# sensor.net
KiCad netlist of a schematic drawn in EAGLE
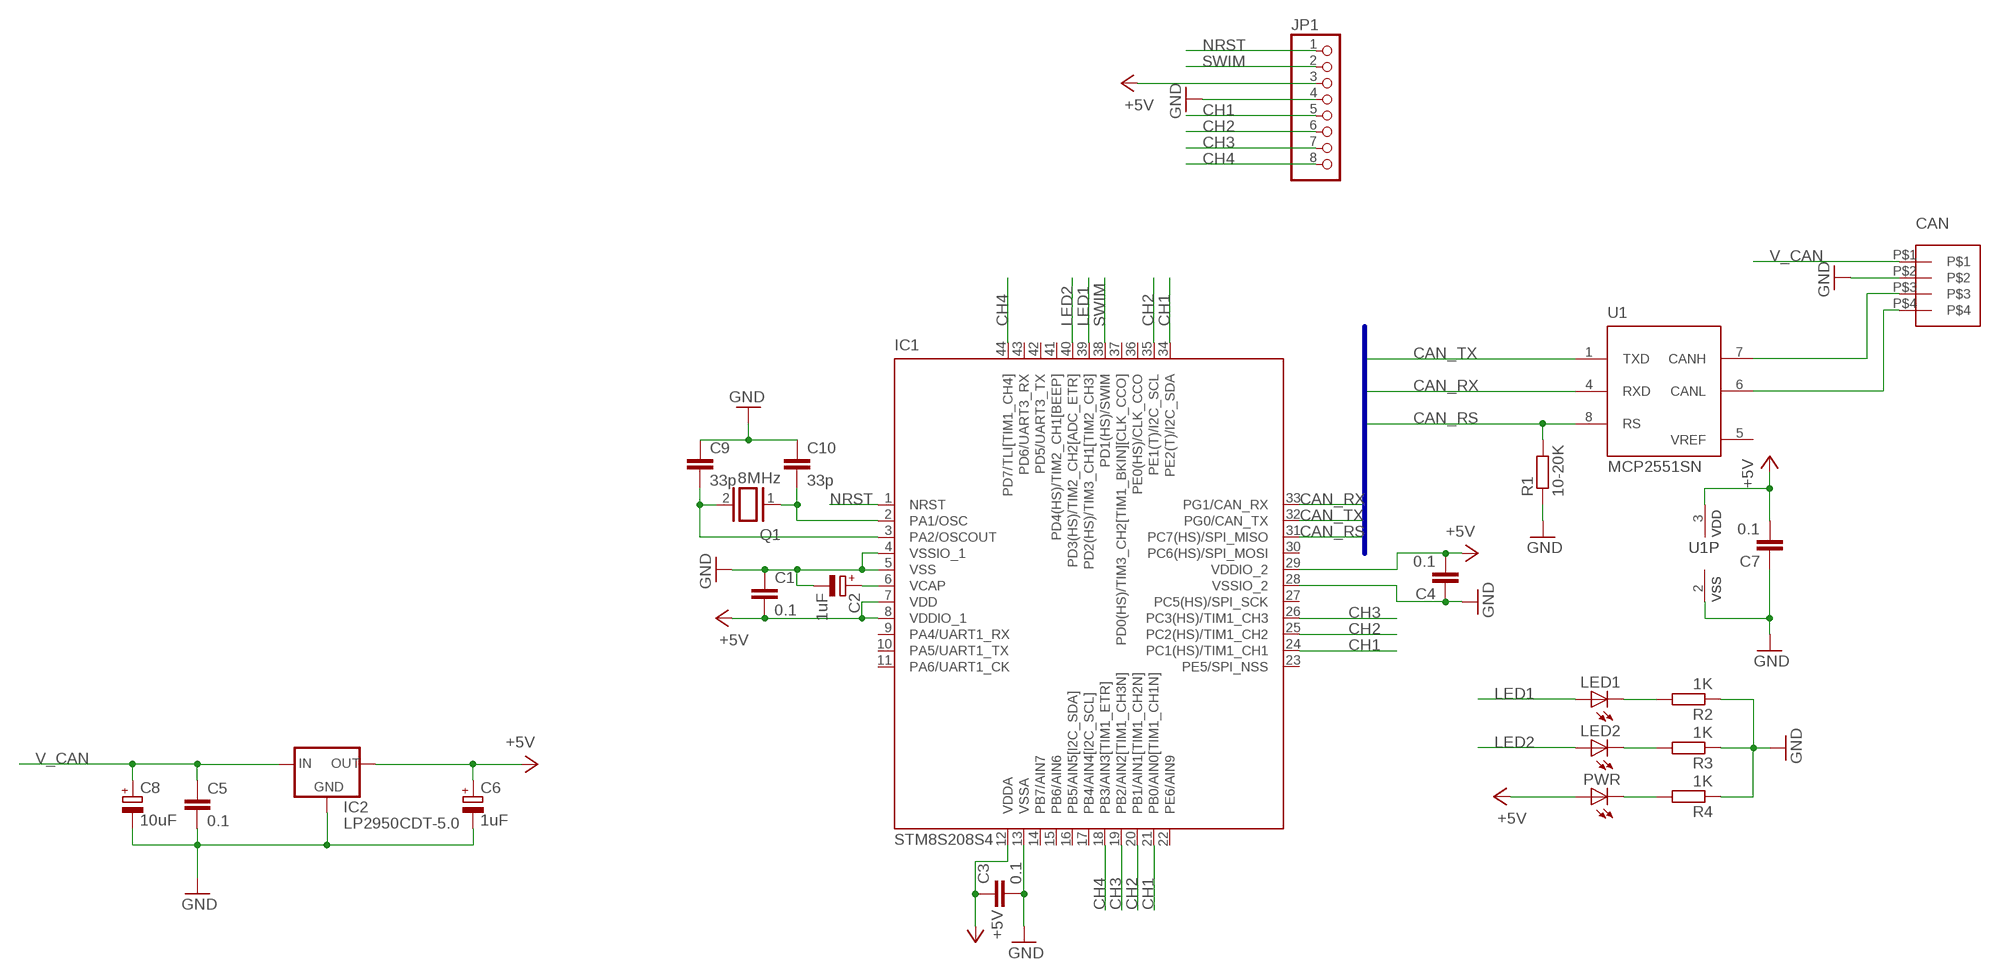
[diagram p0: schematic, sheet 1]

(export (version "E")
  (design (tool "Eeschema 10.0.6"))
  (components
    (comp (ref "C1")
      (value "0.1")
      (footprint "eagle-import:C0805K")
      (libsource (lib "eagle-import") (part "C-EUC0805K"))
    )
    (comp (ref "C2")
      (value "1uF")
      (footprint "eagle-import:E2-4")
      (libsource (lib "eagle-import") (part "CPOL-EUE2-4"))
    )
    (comp (ref "C3")
      (value "0.1")
      (footprint "eagle-import:C0805K")
      (libsource (lib "eagle-import") (part "C-EUC0805K"))
    )
    (comp (ref "C4")
      (value "0.1")
      (footprint "eagle-import:C0805K")
      (libsource (lib "eagle-import") (part "C-EUC0805K"))
    )
    (comp (ref "C5")
      (value "0.1")
      (footprint "eagle-import:C0805K")
      (libsource (lib "eagle-import") (part "C-EUC0805K"))
    )
    (comp (ref "C6")
      (value "1uF")
      (footprint "eagle-import:E2-4")
      (libsource (lib "eagle-import") (part "CPOL-EUE2-4"))
    )
    (comp (ref "C7")
      (value "0.1")
      (footprint "eagle-import:C0805K")
      (libsource (lib "eagle-import") (part "C-EUC0805K"))
    )
    (comp (ref "C8")
      (value "10uF")
      (footprint "eagle-import:E2-4")
      (libsource (lib "eagle-import") (part "CPOL-EUE2-4"))
    )
    (comp (ref "C9")
      (value "33p")
      (footprint "eagle-import:C0805K")
      (libsource (lib "eagle-import") (part "C-EUC0805K"))
    )
    (comp (ref "C10")
      (value "33p")
      (footprint "eagle-import:C0805K")
      (libsource (lib "eagle-import") (part "C-EUC0805K"))
    )
    (comp (ref "CAN")
      (value "CWF-4R")
      (footprint "eagle-import:CWF-4R")
      (libsource (lib "eagle-import") (part "CWF-4R"))
    )
    (comp (ref "IC1")
      (value "STM8S208S4")
      (footprint "eagle-import:LQFP44-10X10")
      (fields (field (name "MPN") "STM8S208S"))
      (libsource (lib "eagle-import") (part "STM8S208S4"))
    )
    (comp (ref "IC2")
      (value "LP2950CDT-5.0")
      (footprint "eagle-import:DPACK")
      (libsource (lib "eagle-import") (part "LP2950?CDT-5.0"))
    )
    (comp (ref "JP1")
      (value "PINHD-1X8/90")
      (footprint "eagle-import:1X08_90")
      (libsource (lib "eagle-import") (part "PINHD-1X8/90"))
    )
    (comp (ref "LED1")
      (value "LEDSML0805")
      (footprint "eagle-import:SML0805")
      (libsource (lib "eagle-import") (part "LEDSML0805"))
    )
    (comp (ref "LED2")
      (value "LEDSML0805")
      (footprint "eagle-import:SML0805")
      (libsource (lib "eagle-import") (part "LEDSML0805"))
    )
    (comp (ref "PWR")
      (value "LEDSML0805")
      (footprint "eagle-import:SML0805")
      (libsource (lib "eagle-import") (part "LEDSML0805"))
    )
    (comp (ref "Q1")
      (value "8MHz")
      (footprint "eagle-import:QS")
      (libsource (lib "eagle-import") (part "XTAL/S"))
    )
    (comp (ref "R1")
      (value "10-20K")
      (footprint "eagle-import:R0805")
      (libsource (lib "eagle-import") (part "R-EU_R0805"))
    )
    (comp (ref "R2")
      (value "1K")
      (footprint "eagle-import:R0805")
      (libsource (lib "eagle-import") (part "R-EU_R0805"))
    )
    (comp (ref "R3")
      (value "1K")
      (footprint "eagle-import:R0805")
      (libsource (lib "eagle-import") (part "R-EU_R0805"))
    )
    (comp (ref "R4")
      (value "1K")
      (footprint "eagle-import:R0805")
      (libsource (lib "eagle-import") (part "R-EU_R0805"))
    )
    (comp (ref "U1")
      (value "MCP2551SN")
      (footprint "eagle-import:SO-08")
      (libsource (lib "eagle-import") (part "MCP2551SN"))
    )
  )
  (nets
    (net (code "1") (name "+5V") (class "Default")
      (node (ref "C1") (pin "2") (pinfunction "2_2") (pintype "passive"))
      (node (ref "C3") (pin "1") (pinfunction "1_1") (pintype "passive"))
      (node (ref "C4") (pin "2") (pinfunction "2_2") (pintype "passive"))
      (node (ref "C6") (pin "+") (pinfunction "+_+") (pintype "passive"))
      (node (ref "C7") (pin "2") (pinfunction "2_2") (pintype "passive"))
      (node (ref "IC1") (pin "12") (pinfunction "VDDA_12") (pintype "power_in"))
      (node (ref "IC1") (pin "29") (pinfunction "VDDIO_2_29") (pintype "power_in"))
      (node (ref "IC1") (pin "7") (pinfunction "VDD_7") (pintype "power_in"))
      (node (ref "IC1") (pin "8") (pinfunction "VDDIO_1_8") (pintype "power_in"))
      (node (ref "IC2") (pin "3") (pinfunction "OUT_3") (pintype "passive"))
      (node (ref "JP1") (pin "3") (pinfunction "3_3") (pintype "passive"))
      (node (ref "PWR") (pin "A") (pinfunction "A_A") (pintype "passive"))
      (node (ref "U1") (pin "3") (pinfunction "VDD_3") (pintype "power_in"))
    )
    (net (code "2") (name "/CAN_RS") (class "Default")
      (node (ref "IC1") (pin "31") (pinfunction "PC7(HS)/SPI_MISO_31") (pintype "bidirectional"))
      (node (ref "R1") (pin "2") (pinfunction "2_2") (pintype "passive"))
      (node (ref "U1") (pin "8") (pinfunction "RS_8") (pintype "input"))
    )
    (net (code "3") (name "/CAN_RX") (class "Default")
      (node (ref "IC1") (pin "33") (pinfunction "PG1/CAN_RX_33") (pintype "bidirectional"))
      (node (ref "U1") (pin "4") (pinfunction "RXD_4") (pintype "output"))
    )
    (net (code "4") (name "/CAN_TX") (class "Default")
      (node (ref "IC1") (pin "32") (pinfunction "PG0/CAN_TX_32") (pintype "bidirectional"))
      (node (ref "U1") (pin "1") (pinfunction "TXD_1") (pintype "input"))
    )
    (net (code "5") (name "/CH1") (class "Default")
      (node (ref "IC1") (pin "21") (pinfunction "PB0/AIN0[TIM1_CH1N]_21") (pintype "bidirectional"))
      (node (ref "IC1") (pin "24") (pinfunction "PC1(HS)/TIM1_CH1_24") (pintype "bidirectional"))
      (node (ref "IC1") (pin "34") (pinfunction "PE2(T)/I2C_SDA_34") (pintype "bidirectional"))
      (node (ref "JP1") (pin "5") (pinfunction "5_5") (pintype "passive"))
    )
    (net (code "6") (name "/CH2") (class "Default")
      (node (ref "IC1") (pin "20") (pinfunction "PB1/AIN1[TIM1_CH2N]_20") (pintype "bidirectional"))
      (node (ref "IC1") (pin "25") (pinfunction "PC2(HS)/TIM1_CH2_25") (pintype "bidirectional"))
      (node (ref "IC1") (pin "35") (pinfunction "PE1(T)/I2C_SCL_35") (pintype "bidirectional"))
      (node (ref "JP1") (pin "6") (pinfunction "6_6") (pintype "passive"))
    )
    (net (code "7") (name "/CH3") (class "Default")
      (node (ref "IC1") (pin "19") (pinfunction "PB2/AIN2[TIM1_CH3N]_19") (pintype "bidirectional"))
      (node (ref "IC1") (pin "26") (pinfunction "PC3(HS)/TIM1_CH3_26") (pintype "bidirectional"))
      (node (ref "JP1") (pin "7") (pinfunction "7_7") (pintype "passive"))
    )
    (net (code "8") (name "/CH4") (class "Default")
      (node (ref "IC1") (pin "18") (pinfunction "PB3/AIN3[TIM1_ETR]_18") (pintype "bidirectional"))
      (node (ref "IC1") (pin "44") (pinfunction "PD7/TLI[TIM1_CH4]_44") (pintype "bidirectional"))
      (node (ref "JP1") (pin "8") (pinfunction "8_8") (pintype "passive"))
    )
    (net (code "9") (name "/LED1") (class "Default")
      (node (ref "IC1") (pin "39") (pinfunction "PD2(HS)/TIM3_CH1[TIM2_CH3]_39") (pintype "bidirectional"))
      (node (ref "LED1") (pin "A") (pinfunction "A_A") (pintype "passive"))
    )
    (net (code "10") (name "/LED2") (class "Default")
      (node (ref "IC1") (pin "40") (pinfunction "PD3(HS)/TIM2_CH2[ADC_ETR]_40") (pintype "bidirectional"))
      (node (ref "LED2") (pin "A") (pinfunction "A_A") (pintype "passive"))
    )
    (net (code "11") (name "/NRST") (class "Default")
      (node (ref "IC1") (pin "1") (pinfunction "NRST_1") (pintype "bidirectional"))
      (node (ref "JP1") (pin "1") (pinfunction "1_1") (pintype "passive"))
    )
    (net (code "12") (name "/SWIM") (class "Default")
      (node (ref "IC1") (pin "38") (pinfunction "PD1(HS)/SWIM_38") (pintype "bidirectional"))
      (node (ref "JP1") (pin "2") (pinfunction "2_2") (pintype "passive"))
    )
    (net (code "13") (name "/VREF") (class "Default")
      (node (ref "U1") (pin "5") (pinfunction "VREF_5") (pintype "power_in"))
    )
    (net (code "14") (name "/V_CAN") (class "Default")
      (node (ref "C5") (pin "1") (pinfunction "1_1") (pintype "passive"))
      (node (ref "C8") (pin "+") (pinfunction "+_+") (pintype "passive"))
      (node (ref "CAN") (pin "P$1") (pinfunction "P$1_P$1") (pintype "bidirectional"))
      (node (ref "IC2") (pin "1") (pinfunction "IN_1") (pintype "input"))
    )
    (net (code "15") (name "GND") (class "Default")
      (node (ref "C1") (pin "1") (pinfunction "1_1") (pintype "passive"))
      (node (ref "C10") (pin "1") (pinfunction "1_1") (pintype "passive"))
      (node (ref "C2") (pin "-") (pinfunction "-_-") (pintype "passive"))
      (node (ref "C3") (pin "2") (pinfunction "2_2") (pintype "passive"))
      (node (ref "C4") (pin "1") (pinfunction "1_1") (pintype "passive"))
      (node (ref "C5") (pin "2") (pinfunction "2_2") (pintype "passive"))
      (node (ref "C6") (pin "-") (pinfunction "-_-") (pintype "passive"))
      (node (ref "C7") (pin "1") (pinfunction "1_1") (pintype "passive"))
      (node (ref "C8") (pin "-") (pinfunction "-_-") (pintype "passive"))
      (node (ref "C9") (pin "1") (pinfunction "1_1") (pintype "passive"))
      (node (ref "CAN") (pin "P$2") (pinfunction "P$2_P$2") (pintype "bidirectional"))
      (node (ref "IC1") (pin "13") (pinfunction "VSSA_13") (pintype "power_in"))
      (node (ref "IC1") (pin "28") (pinfunction "VSSIO_2_28") (pintype "power_in"))
      (node (ref "IC1") (pin "4") (pinfunction "VSSIO_1_4") (pintype "power_in"))
      (node (ref "IC1") (pin "5") (pinfunction "VSS_5") (pintype "power_in"))
      (node (ref "IC2") (pin "4") (pinfunction "GND_4") (pintype "input"))
      (node (ref "JP1") (pin "4") (pinfunction "4_4") (pintype "passive"))
      (node (ref "R1") (pin "1") (pinfunction "1_1") (pintype "passive"))
      (node (ref "R2") (pin "1") (pinfunction "1_1") (pintype "passive"))
      (node (ref "R3") (pin "1") (pinfunction "1_1") (pintype "passive"))
      (node (ref "R4") (pin "1") (pinfunction "1_1") (pintype "passive"))
      (node (ref "U1") (pin "2") (pinfunction "VSS_2") (pintype "power_in"))
    )
    (net (code "16") (name "Net-(IC1-PA1{slash}OSC)") (class "Default")
      (node (ref "C10") (pin "2") (pinfunction "2_2") (pintype "passive"))
      (node (ref "IC1") (pin "2") (pinfunction "PA1/OSC_2") (pintype "bidirectional"))
      (node (ref "Q1") (pin "1") (pinfunction "1_1") (pintype "passive"))
    )
    (net (code "17") (name "Net-(IC1-PA2{slash}OSCOUT)") (class "Default")
      (node (ref "C9") (pin "2") (pinfunction "2_2") (pintype "passive"))
      (node (ref "IC1") (pin "3") (pinfunction "PA2/OSCOUT_3") (pintype "bidirectional"))
      (node (ref "Q1") (pin "2") (pinfunction "2_2") (pintype "passive"))
    )
    (net (code "18") (name "Net-(IC1-VCAP)") (class "Default")
      (node (ref "C2") (pin "+") (pinfunction "+_+") (pintype "passive"))
      (node (ref "IC1") (pin "6") (pinfunction "VCAP_6") (pintype "power_in"))
    )
    (net (code "19") (name "Net-(LED1-PadC)") (class "Default")
      (node (ref "LED1") (pin "C") (pinfunction "C_C") (pintype "passive"))
      (node (ref "R2") (pin "2") (pinfunction "2_2") (pintype "passive"))
    )
    (net (code "20") (name "Net-(LED2-PadC)") (class "Default")
      (node (ref "LED2") (pin "C") (pinfunction "C_C") (pintype "passive"))
      (node (ref "R3") (pin "2") (pinfunction "2_2") (pintype "passive"))
    )
    (net (code "21") (name "Net-(PWR-PadC)") (class "Default")
      (node (ref "PWR") (pin "C") (pinfunction "C_C") (pintype "passive"))
      (node (ref "R4") (pin "2") (pinfunction "2_2") (pintype "passive"))
    )
    (net (code "22") (name "Net-(U1A-CANH)") (class "Default")
      (node (ref "CAN") (pin "P$3") (pinfunction "P$3_P$3") (pintype "bidirectional"))
      (node (ref "U1") (pin "7") (pinfunction "CANH_7") (pintype "bidirectional"))
    )
    (net (code "23") (name "Net-(U1A-CANL)") (class "Default")
      (node (ref "CAN") (pin "P$4") (pinfunction "P$4_P$4") (pintype "bidirectional"))
      (node (ref "U1") (pin "6") (pinfunction "CANL_6") (pintype "bidirectional"))
    )
    (net (code "24") (name "unconnected-(IC1-PA4{slash}UART1_RX-Pad9)") (class "Default")
      (node (ref "IC1") (pin "9") (pinfunction "PA4/UART1_RX_9") (pintype "bidirectional"))
    )
    (net (code "25") (name "unconnected-(IC1-PA5{slash}UART1_TX-Pad10)") (class "Default")
      (node (ref "IC1") (pin "10") (pinfunction "PA5/UART1_TX_10") (pintype "bidirectional"))
    )
    (net (code "26") (name "unconnected-(IC1-PA6{slash}UART1_CK-Pad11)") (class "Default")
      (node (ref "IC1") (pin "11") (pinfunction "PA6/UART1_CK_11") (pintype "bidirectional"))
    )
    (net (code "27") (name "unconnected-(IC1-PB4{slash}AIN4[I2C_SCL]-Pad17)") (class "Default")
      (node (ref "IC1") (pin "17") (pinfunction "PB4/AIN4[I2C_SCL]_17") (pintype "bidirectional"))
    )
    (net (code "28") (name "unconnected-(IC1-PB5{slash}AIN5[I2C_SDA]-Pad16)") (class "Default")
      (node (ref "IC1") (pin "16") (pinfunction "PB5/AIN5[I2C_SDA]_16") (pintype "bidirectional"))
    )
    (net (code "29") (name "unconnected-(IC1-PB6{slash}AIN6-Pad15)") (class "Default")
      (node (ref "IC1") (pin "15") (pinfunction "PB6/AIN6_15") (pintype "bidirectional"))
    )
    (net (code "30") (name "unconnected-(IC1-PB7{slash}AIN7-Pad14)") (class "Default")
      (node (ref "IC1") (pin "14") (pinfunction "PB7/AIN7_14") (pintype "bidirectional"))
    )
    (net (code "31") (name "unconnected-(IC1-PC5(HS){slash}SPI_SCK-Pad27)") (class "Default")
      (node (ref "IC1") (pin "27") (pinfunction "PC5(HS)/SPI_SCK_27") (pintype "bidirectional"))
    )
    (net (code "32") (name "unconnected-(IC1-PC6(HS){slash}SPI_MOSI-Pad30)") (class "Default")
      (node (ref "IC1") (pin "30") (pinfunction "PC6(HS)/SPI_MOSI_30") (pintype "bidirectional"))
    )
    (net (code "33") (name "unconnected-(IC1-PD0(HS){slash}TIM3_CH2[TIM1_BKIN][CLK_CCO]-Pad37)") (class "Default")
      (node (ref "IC1") (pin "37") (pinfunction "PD0(HS)/TIM3_CH2[TIM1_BKIN][CLK_CCO]_37") (pintype "bidirectional"))
    )
    (net (code "34") (name "unconnected-(IC1-PD4(HS){slash}TIM2_CH1[BEEP]-Pad41)") (class "Default")
      (node (ref "IC1") (pin "41") (pinfunction "PD4(HS)/TIM2_CH1[BEEP]_41") (pintype "bidirectional"))
    )
    (net (code "35") (name "unconnected-(IC1-PD5{slash}UART3_TX-Pad42)") (class "Default")
      (node (ref "IC1") (pin "42") (pinfunction "PD5/UART3_TX_42") (pintype "bidirectional"))
    )
    (net (code "36") (name "unconnected-(IC1-PD6{slash}UART3_RX-Pad43)") (class "Default")
      (node (ref "IC1") (pin "43") (pinfunction "PD6/UART3_RX_43") (pintype "bidirectional"))
    )
    (net (code "37") (name "unconnected-(IC1-PE0(HS){slash}CLK_CCO-Pad36)") (class "Default")
      (node (ref "IC1") (pin "36") (pinfunction "PE0(HS)/CLK_CCO_36") (pintype "bidirectional"))
    )
    (net (code "38") (name "unconnected-(IC1-PE5{slash}SPI_NSS-Pad23)") (class "Default")
      (node (ref "IC1") (pin "23") (pinfunction "PE5/SPI_NSS_23") (pintype "bidirectional"))
    )
    (net (code "39") (name "unconnected-(IC1-PE6{slash}AIN9-Pad22)") (class "Default")
      (node (ref "IC1") (pin "22") (pinfunction "PE6/AIN9_22") (pintype "bidirectional"))
    )
  )
)
